# HV.net
KiCad netlist of a schematic drawn in Altium Designer
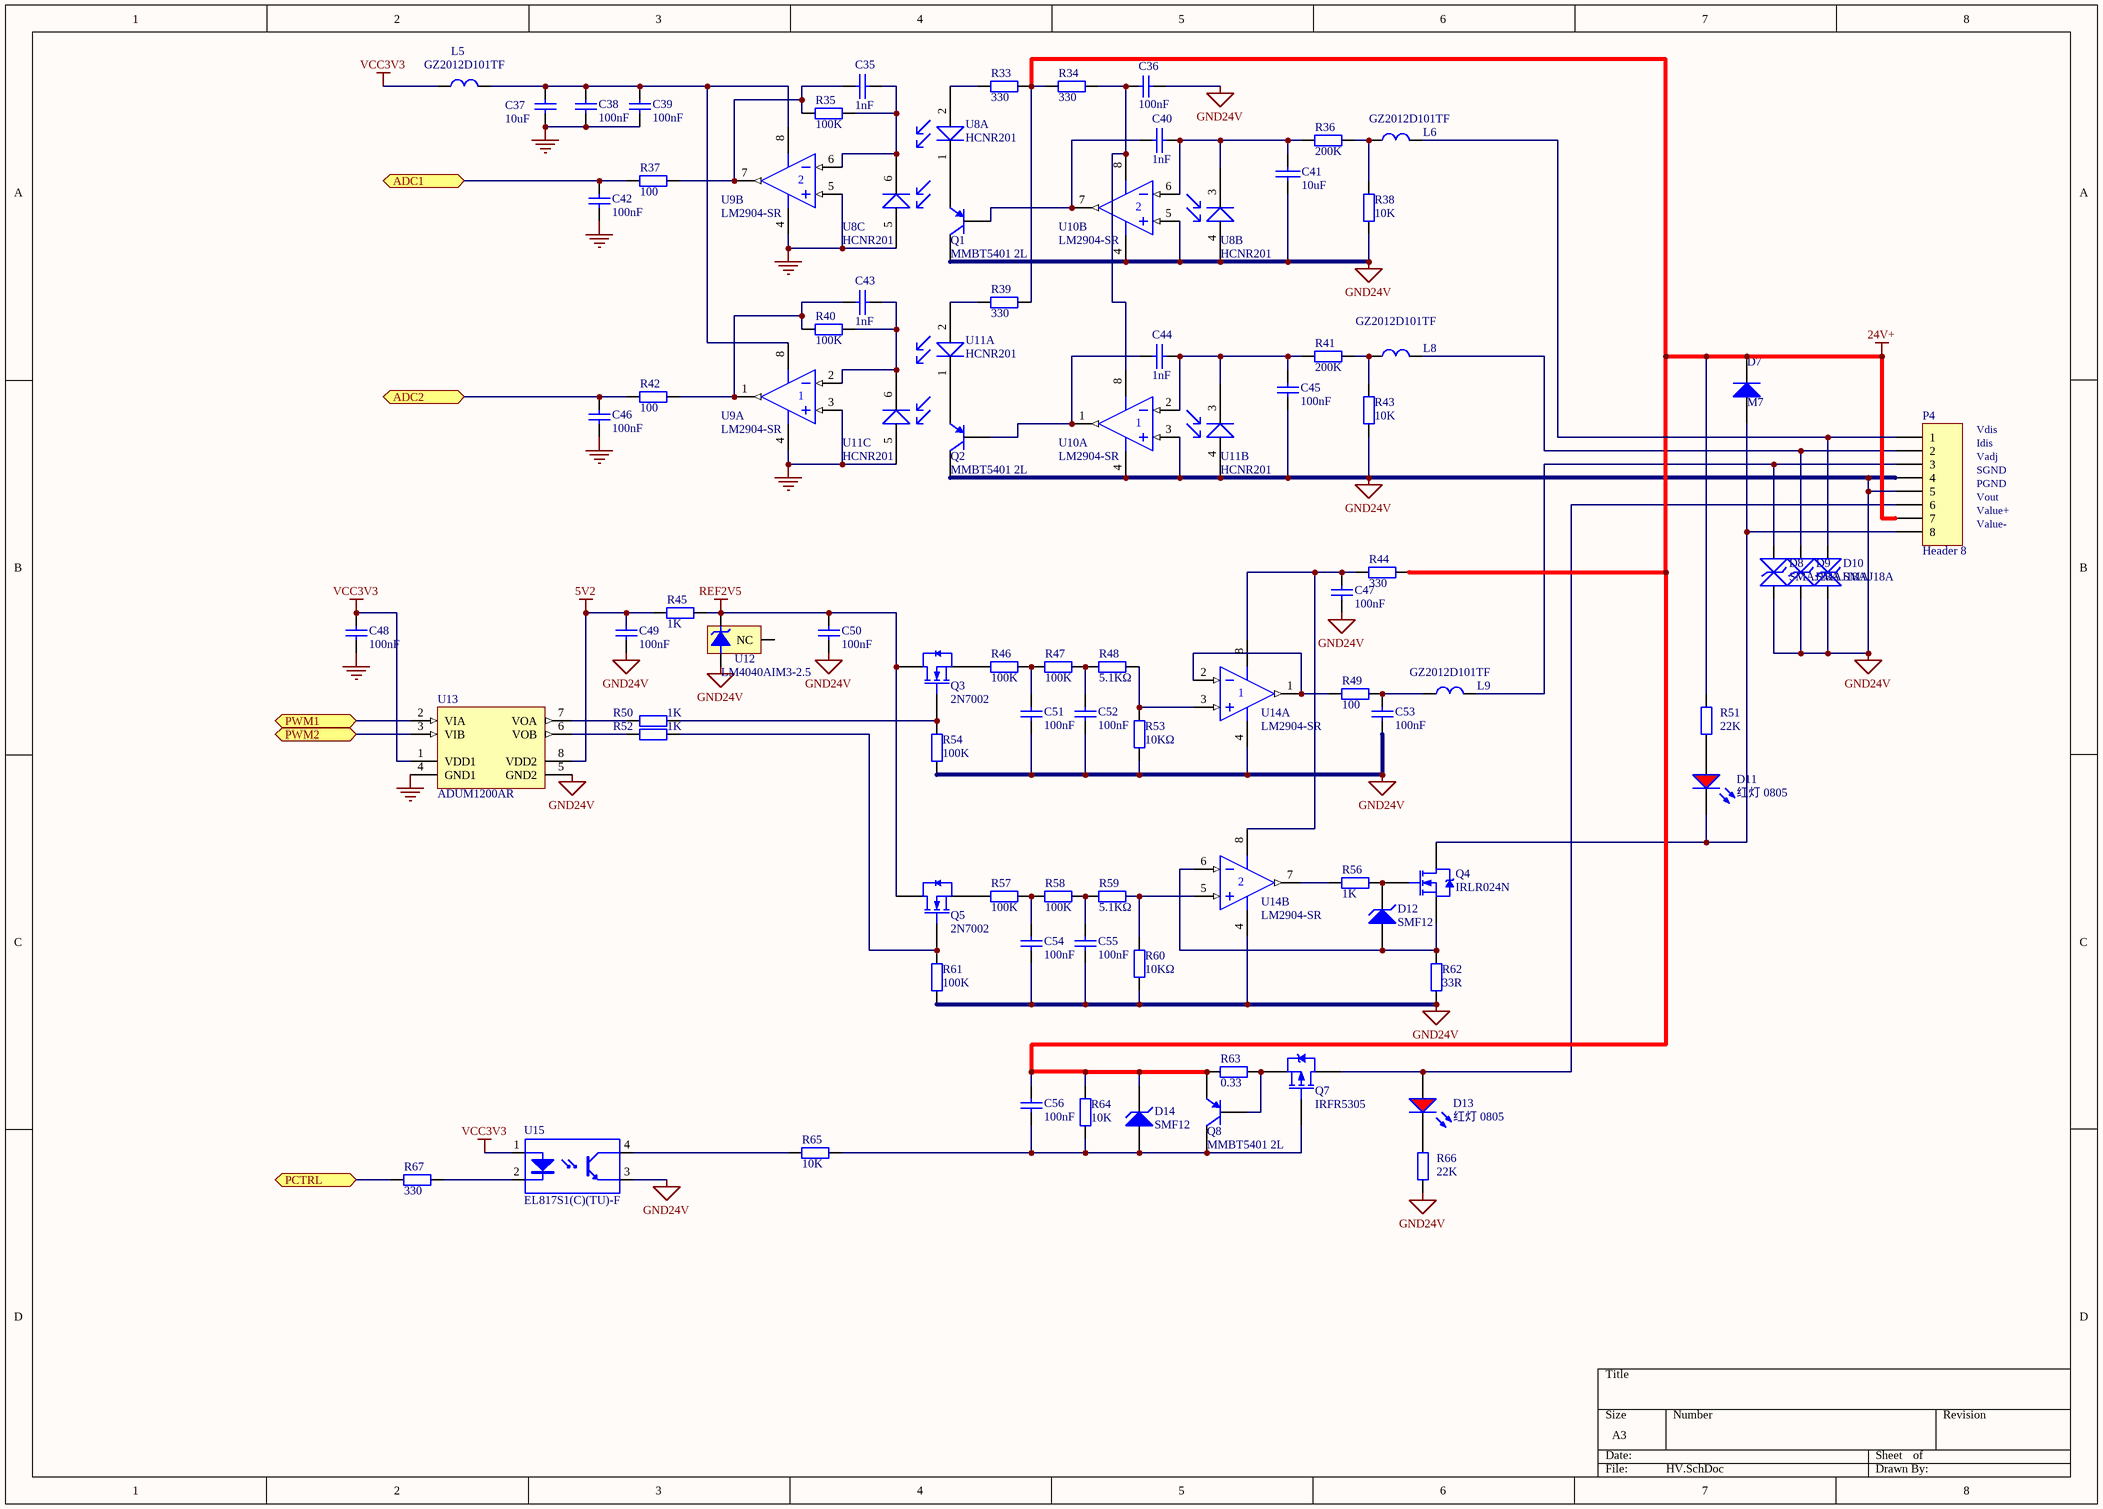
[diagram p0: HV.SchDoc]

(export (version "E")
  (design (tool "Eeschema 10.0.6"))
  (components
    (comp (ref "C35")
      (value "1nF")
      (footprint "0805_C")
      (description "Capacitor")
      (libsource (lib "*") (part "CAP"))
    )
    (comp (ref "C36")
      (value "100nF")
      (footprint "0805_C")
      (description "贴片电容")
      (libsource (lib "Miscellaneous Devices LC") (part "0805 100nF(104) 10% 50V"))
    )
    (comp (ref "C37")
      (value "10uF")
      (footprint "0805_C")
      (description "贴片电容")
      (libsource (lib "Miscellaneous Devices LC") (part "1206 10uF (106) 10% 50V"))
    )
    (comp (ref "C38")
      (value "100nF")
      (footprint "0805_C")
      (description "贴片电容")
      (libsource (lib "Miscellaneous Devices LC") (part "0805 100nF(104) 10% 50V"))
    )
    (comp (ref "C39")
      (value "100nF")
      (footprint "0805_C")
      (description "贴片电容")
      (libsource (lib "Miscellaneous Devices LC") (part "0805 100nF(104) 10% 50V"))
    )
    (comp (ref "C40")
      (value "1nF")
      (footprint "0805_C")
      (description "Capacitor")
      (libsource (lib "*") (part "CAP"))
    )
    (comp (ref "C41")
      (value "10uF")
      (footprint "0805_C")
      (description "Capacitor")
      (libsource (lib "*") (part "CC"))
    )
    (comp (ref "C42")
      (value "100nF")
      (footprint "0805_C")
      (description "贴片电容")
      (libsource (lib "Miscellaneous Devices LC") (part "0805 100nF(104) 10% 50V"))
    )
    (comp (ref "C43")
      (value "1nF")
      (footprint "0805_C")
      (description "Capacitor")
      (libsource (lib "*") (part "CAP"))
    )
    (comp (ref "C44")
      (value "1nF")
      (footprint "0805_C")
      (description "Capacitor")
      (libsource (lib "*") (part "CAP"))
    )
    (comp (ref "C45")
      (value "100nF")
      (footprint "0805_C")
      (description "贴片电容")
      (libsource (lib "Miscellaneous Devices LC") (part "0805 100nF(104) 10% 50V"))
    )
    (comp (ref "C46")
      (value "100nF")
      (footprint "0805_C")
      (description "贴片电容")
      (libsource (lib "Miscellaneous Devices LC") (part "0805 100nF(104) 10% 50V"))
    )
    (comp (ref "C47")
      (value "100nF")
      (footprint "0805_C")
      (description "贴片电容")
      (libsource (lib "Miscellaneous Devices LC") (part "0805 100nF(104) 10% 50V"))
    )
    (comp (ref "C48")
      (value "100nF")
      (footprint "0805_C")
      (description "贴片电容")
      (libsource (lib "Miscellaneous Devices LC") (part "0805 100nF(104) 10% 50V"))
    )
    (comp (ref "C49")
      (value "100nF")
      (footprint "0805_C")
      (description "贴片电容")
      (libsource (lib "Miscellaneous Devices LC") (part "0805 100nF(104) 10% 50V"))
    )
    (comp (ref "C50")
      (value "100nF")
      (footprint "0805_C")
      (description "贴片电容")
      (libsource (lib "Miscellaneous Devices LC") (part "0805 100nF(104) 10% 50V"))
    )
    (comp (ref "C51")
      (value "100nF")
      (footprint "0805_C")
      (description "贴片电容")
      (libsource (lib "Miscellaneous Devices LC") (part "0805 100nF(104) 10% 50V"))
    )
    (comp (ref "C52")
      (value "100nF")
      (footprint "0805_C")
      (description "贴片电容")
      (libsource (lib "Miscellaneous Devices LC") (part "0805 100nF(104) 10% 50V"))
    )
    (comp (ref "C53")
      (value "100nF")
      (footprint "0805_C")
      (description "贴片电容")
      (libsource (lib "Miscellaneous Devices LC") (part "0805 100nF(104) 10% 50V"))
    )
    (comp (ref "C54")
      (value "100nF")
      (footprint "0805_C")
      (description "贴片电容")
      (libsource (lib "Miscellaneous Devices LC") (part "0805 100nF(104) 10% 50V"))
    )
    (comp (ref "C55")
      (value "100nF")
      (footprint "0805_C")
      (description "贴片电容")
      (libsource (lib "Miscellaneous Devices LC") (part "0805 100nF(104) 10% 50V"))
    )
    (comp (ref "C56")
      (value "100nF")
      (footprint "0805_C")
      (description "贴片电容")
      (libsource (lib "Miscellaneous Devices LC") (part "0805 100nF(104) 10% 50V"))
    )
    (comp (ref "D7")
      (value "M7")
      (footprint "SMA(DO-214AC)_S1")
      (description "二极管")
      (libsource (lib "Miscellaneous Devices LC") (part "SMA(DO-214AC) M7"))
    )
    (comp (ref "D8") (value "SMAJ18A") (footprint "SMA") (libsource (lib "IC") (part "TVS")))
    (comp (ref "D9") (value "SMAJ18A") (footprint "SMA") (libsource (lib "IC") (part "TVS")))
    (comp (ref "D10") (value "SMAJ18A") (footprint "SMA") (libsource (lib "IC") (part "TVS")))
    (comp (ref "D11")
      (value "红灯 0805")
      (footprint "0805_LED_S1")
      (description "发光二极管")
      (libsource (lib "Miscellaneous Devices LC") (part "0805 红灯"))
    )
    (comp (ref "D12")
      (value "SMF12")
      (footprint "Miscellaneous Devices LC:SOD-123")
      (description "Zener Diode")
      (fields (field (name "PUBLISHER") "Altium Limited"))
      (libsource (lib "Miscellaneous Devices") (part "D Zener"))
    )
    (comp (ref "D13")
      (value "红灯 0805")
      (footprint "0805_LED_S1")
      (description "发光二极管")
      (libsource (lib "Miscellaneous Devices LC") (part "0805 红灯"))
    )
    (comp (ref "D14")
      (value "SMF12")
      (footprint "Miscellaneous Devices LC:SOD-123")
      (description "Zener Diode")
      (fields (field (name "PUBLISHER") "Altium Limited"))
      (libsource (lib "Miscellaneous Devices") (part "D Zener"))
    )
    (comp (ref "L5") (value "GZ2012D101TF") (footprint "0805_L") (libsource (lib "Devices") (part "L1")))
    (comp (ref "L6") (value "GZ2012D101TF") (footprint "0805_L") (libsource (lib "Devices") (part "L1")))
    (comp (ref "L8") (value "GZ2012D101TF") (footprint "0805_L") (libsource (lib "Devices") (part "L1")))
    (comp (ref "L9") (value "GZ2012D101TF") (footprint "0805_L") (libsource (lib "") (part "L1_1")))
    (comp (ref "P4")
      (value "Header 8")
      (footprint "MC1.5/8-ST-3.81")
      (description "Header, 8-Pin")
      (fields (field (name "PUBLISHER") "Altium Limited"))
      (libsource (lib "Miscellaneous Connectors") (part "Header 8"))
    )
    (comp (ref "Q1")
      (value "MMBT5401 2L")
      (footprint "SOT-23(SOT-23-3)")
      (description "三极管")
      (libsource (lib "Miscellaneous Devices LC") (part "SOT-23 MMBT5401 2L"))
    )
    (comp (ref "Q2")
      (value "MMBT5401 2L")
      (footprint "SOT-23(SOT-23-3)")
      (description "三极管")
      (libsource (lib "Miscellaneous Devices LC") (part "SOT-23 MMBT5401 2L"))
    )
    (comp (ref "Q3")
      (value "2N7002")
      (footprint "SOT-23(SOT-23-3)")
      (description "MOS(场效应管)")
      (libsource (lib "Miscellaneous Devices LC") (part "2N7002 7002"))
    )
    (comp (ref "Q4")
      (value "IRLR024N")
      (footprint "TO-252AA_N")
      (description "HEXFET Power MOSFET")
      (fields (field (name "PUBLISHER") "Altium Limited"))
      (libsource (lib "IR Discrete MOSFET - Power") (part "IRLR024N"))
    )
    (comp (ref "Q5")
      (value "2N7002")
      (footprint "SOT-23(SOT-23-3)")
      (description "MOS(场效应管)")
      (libsource (lib "Miscellaneous Devices LC") (part "2N7002 7002"))
    )
    (comp (ref "Q7")
      (value "IRFR5305")
      (footprint "TO-252AA_N")
      (description "HEXFET Power MOSFET")
      (fields (field (name "PUBLISHER") "Altium Limited"))
      (libsource (lib "IR Discrete MOSFET - Power") (part "IRFR5305"))
    )
    (comp (ref "Q8")
      (value "MMBT5401 2L")
      (footprint "SOT-23(SOT-23-3)")
      (description "三极管")
      (libsource (lib "Miscellaneous Devices LC") (part "SOT-23 MMBT5401 2L"))
    )
    (comp (ref "R33")
      (value "330")
      (footprint "0805_R")
      (description "Resistor")
      (fields (field (name "PUBLISHER") "Altium Limited"))
      (libsource (lib "") (part "Res2_1"))
    )
    (comp (ref "R34")
      (value "330")
      (footprint "0805_R")
      (description "Resistor")
      (fields (field (name "PUBLISHER") "Altium Limited"))
      (libsource (lib "") (part "Res2_1"))
    )
    (comp (ref "R35")
      (value "100K")
      (footprint "0805_R")
      (description "Resistor")
      (fields (field (name "PUBLISHER") "Altium Limited"))
      (libsource (lib "Miscellaneous Devices") (part "Res2"))
    )
    (comp (ref "R36")
      (value "200K")
      (footprint "0805_R")
      (description "Resistor")
      (fields (field (name "PUBLISHER") "Altium Limited"))
      (libsource (lib "Miscellaneous Devices") (part "Res2"))
    )
    (comp (ref "R37")
      (value "100")
      (footprint "0805_R")
      (description "Resistor")
      (fields (field (name "PUBLISHER") "Altium Limited"))
      (libsource (lib "") (part "Res2_1"))
    )
    (comp (ref "R38")
      (value "10K")
      (footprint "0805_R")
      (description "Resistor")
      (fields (field (name "PUBLISHER") "Altium Limited"))
      (libsource (lib "") (part "Res2_2"))
    )
    (comp (ref "R39")
      (value "330")
      (footprint "0805_R")
      (description "Resistor")
      (fields (field (name "PUBLISHER") "Altium Limited"))
      (libsource (lib "") (part "Res2_1"))
    )
    (comp (ref "R40")
      (value "100K")
      (footprint "0805_R")
      (description "Resistor")
      (fields (field (name "PUBLISHER") "Altium Limited"))
      (libsource (lib "Miscellaneous Devices") (part "Res2"))
    )
    (comp (ref "R41")
      (value "200K")
      (footprint "0805_R")
      (description "Resistor")
      (fields (field (name "PUBLISHER") "Altium Limited"))
      (libsource (lib "Miscellaneous Devices") (part "Res2"))
    )
    (comp (ref "R42")
      (value "100")
      (footprint "0805_R")
      (description "Resistor")
      (fields (field (name "PUBLISHER") "Altium Limited"))
      (libsource (lib "") (part "Res2_1"))
    )
    (comp (ref "R43")
      (value "10K")
      (footprint "0805_R")
      (description "Resistor")
      (fields (field (name "PUBLISHER") "Altium Limited"))
      (libsource (lib "") (part "Res2_2"))
    )
    (comp (ref "R44")
      (value "330")
      (footprint "0805_R")
      (description "贴片电阻")
      (libsource (lib "Miscellaneous Devices LC") (part "0805 100Ω (1000) 1%"))
    )
    (comp (ref "R45")
      (value "1K")
      (footprint "0805_R")
      (description "贴片电阻")
      (libsource (lib "") (part "0805 100KΩ (1003) 1%_1"))
    )
    (comp (ref "R46")
      (value "100K")
      (footprint "0805_R")
      (description "贴片电阻")
      (libsource (lib "") (part "0805 100KΩ (1003) 1%_1"))
    )
    (comp (ref "R47")
      (value "100K")
      (footprint "0805_R")
      (description "贴片电阻")
      (libsource (lib "") (part "0805 100KΩ (1003) 1%_1"))
    )
    (comp (ref "R48")
      (value "5.1KΩ")
      (footprint "0805_R")
      (description "贴片电阻")
      (libsource (lib "Miscellaneous Devices LC") (part "0805 5.1KΩ (5101) 1%"))
    )
    (comp (ref "R49")
      (value "100")
      (footprint "0805_R")
      (description "贴片电阻")
      (libsource (lib "") (part "0805 100KΩ (1003) 1%_1"))
    )
    (comp (ref "R50")
      (value "1K")
      (footprint "0805_R")
      (description "贴片电阻")
      (libsource (lib "") (part "0805 100KΩ (1003) 1%_2"))
    )
    (comp (ref "R51")
      (value "22K")
      (footprint "R0805")
      (description "贴片电阻")
      (libsource (lib "电阻") (part "RMK2012KBxxx（10～1M）F"))
    )
    (comp (ref "R52")
      (value "1K")
      (footprint "0805_R")
      (description "贴片电阻")
      (libsource (lib "") (part "0805 100KΩ (1003) 1%_2"))
    )
    (comp (ref "R53")
      (value "10KΩ")
      (footprint "0805_R")
      (description "贴片电阻")
      (libsource (lib "Miscellaneous Devices LC") (part "0805 10KΩ (1002) 1%"))
    )
    (comp (ref "R54")
      (value "100K")
      (footprint "0805_R")
      (description "贴片电阻")
      (libsource (lib "Miscellaneous Devices LC") (part "0805 100KΩ (1003) 1%"))
    )
    (comp (ref "R56")
      (value "1K")
      (footprint "0805_R")
      (description "贴片电阻")
      (libsource (lib "") (part "0805 100KΩ (1003) 1%_1"))
    )
    (comp (ref "R57")
      (value "100K")
      (footprint "0805_R")
      (description "贴片电阻")
      (libsource (lib "") (part "0805 100KΩ (1003) 1%_1"))
    )
    (comp (ref "R58")
      (value "100K")
      (footprint "0805_R")
      (description "贴片电阻")
      (libsource (lib "") (part "0805 100KΩ (1003) 1%_1"))
    )
    (comp (ref "R59")
      (value "5.1KΩ")
      (footprint "0805_R")
      (description "贴片电阻")
      (libsource (lib "Miscellaneous Devices LC") (part "0805 5.1KΩ (5101) 1%"))
    )
    (comp (ref "R60")
      (value "10KΩ")
      (footprint "0805_R")
      (description "贴片电阻")
      (libsource (lib "Miscellaneous Devices LC") (part "0805 10KΩ (1002) 1%"))
    )
    (comp (ref "R61")
      (value "100K")
      (footprint "0805_R")
      (description "贴片电阻")
      (libsource (lib "Miscellaneous Devices LC") (part "0805 100KΩ (1003) 1%"))
    )
    (comp (ref "R62")
      (value "33R")
      (footprint "R2512")
      (description "Resistor")
      (fields (field (name "PUBLISHER") "Altium Limited"))
      (libsource (lib "") (part "Res2_4"))
    )
    (comp (ref "R63")
      (value "0.33")
      (footprint "R2512")
      (description "Resistor")
      (fields (field (name "PUBLISHER") "Altium Limited"))
      (libsource (lib "") (part "Res2_3"))
    )
    (comp (ref "R64")
      (value "10K")
      (footprint "0805_R")
      (description "Resistor")
      (fields (field (name "PUBLISHER") "Altium Limited"))
      (libsource (lib "") (part "Res2_4"))
    )
    (comp (ref "R65")
      (value "10K")
      (footprint "0805_R")
      (description "Resistor")
      (fields (field (name "PUBLISHER") "Altium Limited"))
      (libsource (lib "") (part "Res2_3"))
    )
    (comp (ref "R66")
      (value "22K")
      (footprint "0805_R")
      (description "贴片电阻")
      (libsource (lib "电阻") (part "RMK2012KBxxx（10～1M）F"))
    )
    (comp (ref "R67")
      (value "330")
      (footprint "0805_R")
      (description "Resistor")
      (fields (field (name "PUBLISHER") "Altium Limited"))
      (libsource (lib "") (part "Res2_5"))
    )
    (comp (ref "U8") (value "HCNR201") (footprint "SMD-8_9.0mm") (libsource (lib "*") (part "HCNR201")))
    (comp (ref "U9")
      (value "LM2904-SR")
      (footprint "SOIC-8_150mil")
      (description "Dual Low-Power Operational Amplifier")
      (fields (field (name "PUBLISHER") "Altium Limited"))
      (libsource (lib "Miscellaneous Devices LC") (part "LM2904D"))
    )
    (comp (ref "U10")
      (value "LM2904-SR")
      (footprint "SOIC-8_150mil")
      (description "Dual Low-Power Operational Amplifier")
      (fields (field (name "PUBLISHER") "Altium Limited"))
      (libsource (lib "Miscellaneous Devices LC") (part "LM2904D"))
    )
    (comp (ref "U11") (value "HCNR201") (footprint "SMD-8_9.0mm") (libsource (lib "*") (part "HCNR201")))
    (comp (ref "U12")
      (value "LM4040AIM3-2.5")
      (footprint "MF03A_N")
      (description "Precision Micropower Shunt Voltage Reference, 3-pin SOT-23")
      (fields (field (name "MANUFACTURER") "National Semiconductor"))
      (libsource (lib "National Semiconductor Voltage Reference") (part "LM4040AIM3-2.5"))
    )
    (comp (ref "U13")
      (value "ADUM1200AR")
      (footprint "ADI-R-8_N")
      (fields (field (name "MANUFACTURER") "Analog Devices"))
      (libsource (lib "Analog Devices Interface and Isolation Digital Isolators") (part "ADUM1200AR"))
    )
    (comp (ref "U14")
      (value "LM2904-SR")
      (footprint "SOIC-8_150mil")
      (description "Dual Low-Power Operational Amplifier")
      (fields (field (name "PUBLISHER") "Altium Limited"))
      (libsource (lib "Miscellaneous Devices LC") (part "LM2904D"))
    )
    (comp (ref "U15")
      (value "EL817S1(C)(TU)-F")
      (footprint "LC-SMD-4")
      (libsource (lib "IC") (part "TLP521"))
    )
  )
  (nets
    (net (code "1") (name "/ADC1") (class "Default")
      (node (ref "C42") (pin "2") (pinfunction "2_2") (pintype "passive"))
      (node (ref "R37") (pin "2") (pinfunction "2_2") (pintype "passive"))
    )
    (net (code "2") (name "/ADC2") (class "Default")
      (node (ref "C46") (pin "2") (pinfunction "2_2") (pintype "passive"))
      (node (ref "R42") (pin "2") (pinfunction "2_2") (pintype "passive"))
    )
    (net (code "3") (name "/PCTRL") (class "Default")
      (node (ref "R67") (pin "1") (pinfunction "1_1") (pintype "passive"))
    )
    (net (code "4") (name "/PWM1") (class "Default")
      (node (ref "U13") (pin "2") (pinfunction "VIA_2") (pintype "input"))
    )
    (net (code "5") (name "/PWM2") (class "Default")
      (node (ref "U13") (pin "3") (pinfunction "VIB_3") (pintype "input"))
    )
    (net (code "6") (name "5V2") (class "Default")
      (node (ref "C49") (pin "2") (pinfunction "2_2") (pintype "passive"))
      (node (ref "R45") (pin "2") (pinfunction "2_2") (pintype "passive"))
      (node (ref "U13") (pin "8") (pinfunction "VDD2_8") (pintype "power_in"))
    )
    (net (code "7") (name "24V+") (class "Default")
      (node (ref "C56") (pin "2") (pinfunction "2_2") (pintype "passive"))
      (node (ref "D14") (pin "2") (pinfunction "K_2") (pintype "passive"))
      (node (ref "D7") (pin "2") (pinfunction "K_2") (pintype "passive"))
      (node (ref "P4") (pin "7") (pinfunction "7_7") (pintype "passive"))
      (node (ref "Q8") (pin "2") (pinfunction "E_2") (pintype "passive"))
      (node (ref "R33") (pin "1") (pinfunction "1_1") (pintype "passive"))
      (node (ref "R34") (pin "2") (pinfunction "2_2") (pintype "passive"))
      (node (ref "R39") (pin "1") (pinfunction "1_1") (pintype "passive"))
      (node (ref "R44") (pin "1") (pinfunction "1_1") (pintype "passive"))
      (node (ref "R51") (pin "1") (pinfunction "1_1") (pintype "passive"))
      (node (ref "R63") (pin "2") (pinfunction "2_2") (pintype "passive"))
      (node (ref "R64") (pin "2") (pinfunction "2_2") (pintype "passive"))
    )
    (net (code "8") (name "GND") (class "Default")
      (node (ref "C37") (pin "1") (pinfunction "1_1") (pintype "passive"))
      (node (ref "C38") (pin "1") (pinfunction "1_1") (pintype "passive"))
      (node (ref "C39") (pin "1") (pinfunction "1_1") (pintype "passive"))
      (node (ref "C42") (pin "1") (pinfunction "1_1") (pintype "passive"))
      (node (ref "C46") (pin "1") (pinfunction "1_1") (pintype "passive"))
      (node (ref "C48") (pin "1") (pinfunction "1_1") (pintype "passive"))
      (node (ref "U11") (pin "5") (pinfunction "+_5") (pintype "passive"))
      (node (ref "U13") (pin "4") (pinfunction "GND1_4") (pintype "power_in"))
      (node (ref "U8") (pin "5") (pinfunction "+_5") (pintype "passive"))
      (node (ref "U9") (pin "3") (pinfunction "IN+_3") (pintype "input"))
      (node (ref "U9") (pin "4") (pinfunction "V-_4") (pintype "power_in"))
      (node (ref "U9") (pin "5") (pinfunction "IN+_5") (pintype "input"))
    )
    (net (code "9") (name "GND24V") (class "Default")
      (node (ref "C36") (pin "1") (pinfunction "1_1") (pintype "passive"))
      (node (ref "C41") (pin "1") (pinfunction "1_1") (pintype "passive"))
      (node (ref "C45") (pin "1") (pinfunction "1_1") (pintype "passive"))
      (node (ref "C47") (pin "1") (pinfunction "1_1") (pintype "passive"))
      (node (ref "C49") (pin "1") (pinfunction "1_1") (pintype "passive"))
      (node (ref "C50") (pin "1") (pinfunction "1_1") (pintype "passive"))
      (node (ref "C51") (pin "1") (pinfunction "1_1") (pintype "passive"))
      (node (ref "C52") (pin "1") (pinfunction "1_1") (pintype "passive"))
      (node (ref "C53") (pin "1") (pinfunction "1_1") (pintype "passive"))
      (node (ref "C54") (pin "1") (pinfunction "1_1") (pintype "passive"))
      (node (ref "C55") (pin "1") (pinfunction "1_1") (pintype "passive"))
      (node (ref "D10") (pin "1") (pinfunction "1_1") (pintype "passive"))
      (node (ref "D8") (pin "1") (pinfunction "1_1") (pintype "passive"))
      (node (ref "D9") (pin "1") (pinfunction "1_1") (pintype "passive"))
      (node (ref "P4") (pin "4") (pinfunction "4_4") (pintype "passive"))
      (node (ref "P4") (pin "5") (pinfunction "5_5") (pintype "passive"))
      (node (ref "Q1") (pin "3") (pinfunction "C_3") (pintype "passive"))
      (node (ref "Q2") (pin "3") (pinfunction "C_3") (pintype "passive"))
      (node (ref "R38") (pin "1") (pinfunction "1_1") (pintype "passive"))
      (node (ref "R43") (pin "1") (pinfunction "1_1") (pintype "passive"))
      (node (ref "R53") (pin "2") (pinfunction "2_2") (pintype "passive"))
      (node (ref "R54") (pin "2") (pinfunction "2_2") (pintype "passive"))
      (node (ref "R60") (pin "2") (pinfunction "2_2") (pintype "passive"))
      (node (ref "R61") (pin "2") (pinfunction "2_2") (pintype "passive"))
      (node (ref "R62") (pin "1") (pinfunction "1_1") (pintype "passive"))
      (node (ref "R66") (pin "2") (pinfunction "2_2") (pintype "passive"))
      (node (ref "U10") (pin "3") (pinfunction "IN+_3") (pintype "input"))
      (node (ref "U10") (pin "4") (pinfunction "V-_4") (pintype "power_in"))
      (node (ref "U10") (pin "5") (pinfunction "IN+_5") (pintype "input"))
      (node (ref "U11") (pin "4") (pinfunction "+_4") (pintype "passive"))
      (node (ref "U12") (pin "2") (pinfunction "-V_2") (pintype "passive"))
      (node (ref "U13") (pin "5") (pinfunction "GND2_5") (pintype "power_in"))
      (node (ref "U14") (pin "4") (pinfunction "V-_4") (pintype "power_in"))
      (node (ref "U15") (pin "3") (pinfunction "E_3") (pintype "passive"))
      (node (ref "U8") (pin "4") (pinfunction "+_4") (pintype "passive"))
    )
    (net (code "10") (name "Net-(C51-Pad2)") (class "Default")
      (node (ref "C51") (pin "2") (pinfunction "2_2") (pintype "passive"))
      (node (ref "R46") (pin "1") (pinfunction "1_1") (pintype "passive"))
      (node (ref "R47") (pin "2") (pinfunction "2_2") (pintype "passive"))
    )
    (net (code "11") (name "Net-(C52-Pad2)") (class "Default")
      (node (ref "C52") (pin "2") (pinfunction "2_2") (pintype "passive"))
      (node (ref "R47") (pin "1") (pinfunction "1_1") (pintype "passive"))
      (node (ref "R48") (pin "2") (pinfunction "2_2") (pintype "passive"))
    )
    (net (code "12") (name "Net-(C53-Pad2)") (class "Default")
      (node (ref "C53") (pin "2") (pinfunction "2_2") (pintype "passive"))
      (node (ref "L9") (pin "2") (pinfunction "2_2") (pintype "passive"))
      (node (ref "R49") (pin "1") (pinfunction "1_1") (pintype "passive"))
    )
    (net (code "13") (name "Net-(C54-Pad2)") (class "Default")
      (node (ref "C54") (pin "2") (pinfunction "2_2") (pintype "passive"))
      (node (ref "R57") (pin "1") (pinfunction "1_1") (pintype "passive"))
      (node (ref "R58") (pin "2") (pinfunction "2_2") (pintype "passive"))
    )
    (net (code "14") (name "Net-(C55-Pad2)") (class "Default")
      (node (ref "C55") (pin "2") (pinfunction "2_2") (pintype "passive"))
      (node (ref "R58") (pin "1") (pinfunction "1_1") (pintype "passive"))
      (node (ref "R59") (pin "2") (pinfunction "2_2") (pintype "passive"))
    )
    (net (code "15") (name "Net-(D7-A)") (class "Default")
      (node (ref "D11") (pin "K") (pinfunction "K_K") (pintype "passive"))
      (node (ref "D7") (pin "1") (pinfunction "A_1") (pintype "passive"))
      (node (ref "P4") (pin "8") (pinfunction "8_8") (pintype "passive"))
      (node (ref "Q4") (pin "4") (pinfunction "D_4") (pintype "passive"))
    )
    (net (code "16") (name "Net-(D8-Pad2)") (class "Default")
      (node (ref "D8") (pin "2") (pinfunction "2_2") (pintype "passive"))
      (node (ref "L9") (pin "1") (pinfunction "1_1") (pintype "passive"))
      (node (ref "P4") (pin "3") (pinfunction "3_3") (pintype "passive"))
    )
    (net (code "17") (name "Net-(D9-Pad2)") (class "Default")
      (node (ref "D9") (pin "2") (pinfunction "2_2") (pintype "passive"))
      (node (ref "L8") (pin "2") (pinfunction "2_2") (pintype "passive"))
      (node (ref "P4") (pin "2") (pinfunction "2_2") (pintype "passive"))
    )
    (net (code "18") (name "Net-(D10-Pad2)") (class "Default")
      (node (ref "D10") (pin "2") (pinfunction "2_2") (pintype "passive"))
      (node (ref "L6") (pin "2") (pinfunction "2_2") (pintype "passive"))
      (node (ref "P4") (pin "1") (pinfunction "1_1") (pintype "passive"))
    )
    (net (code "19") (name "Net-(D11-PadA)") (class "Default")
      (node (ref "D11") (pin "A") (pinfunction "A_A") (pintype "passive"))
      (node (ref "R51") (pin "2") (pinfunction "2_2") (pintype "passive"))
    )
    (net (code "20") (name "Net-(D12-A)") (class "Default")
      (node (ref "D12") (pin "1") (pinfunction "A_1") (pintype "passive"))
      (node (ref "Q4") (pin "3") (pinfunction "S_3") (pintype "passive"))
      (node (ref "R62") (pin "2") (pinfunction "2_2") (pintype "passive"))
      (node (ref "U14") (pin "6") (pinfunction "IN-_6") (pintype "input"))
    )
    (net (code "21") (name "Net-(D12-K)") (class "Default")
      (node (ref "D12") (pin "2") (pinfunction "K_2") (pintype "passive"))
      (node (ref "Q4") (pin "1") (pinfunction "G_1") (pintype "passive"))
      (node (ref "R56") (pin "1") (pinfunction "1_1") (pintype "passive"))
    )
    (net (code "22") (name "Net-(D13-PadK)") (class "Default")
      (node (ref "D13") (pin "K") (pinfunction "K_K") (pintype "passive"))
      (node (ref "R66") (pin "1") (pinfunction "1_1") (pintype "passive"))
    )
    (net (code "23") (name "Net-(D14-A)") (class "Default")
      (node (ref "C56") (pin "1") (pinfunction "1_1") (pintype "passive"))
      (node (ref "D14") (pin "1") (pinfunction "A_1") (pintype "passive"))
      (node (ref "Q7") (pin "1") (pinfunction "G_1") (pintype "passive"))
      (node (ref "Q8") (pin "3") (pinfunction "C_3") (pintype "passive"))
      (node (ref "R64") (pin "1") (pinfunction "1_1") (pintype "passive"))
      (node (ref "R65") (pin "1") (pinfunction "1_1") (pintype "passive"))
    )
    (net (code "24") (name "Net-(L6-Pad1)") (class "Default")
      (node (ref "L6") (pin "1") (pinfunction "1_1") (pintype "passive"))
      (node (ref "R36") (pin "2") (pinfunction "2_2") (pintype "passive"))
      (node (ref "R38") (pin "2") (pinfunction "2_2") (pintype "passive"))
    )
    (net (code "25") (name "Net-(L8-Pad1)") (class "Default")
      (node (ref "L8") (pin "1") (pinfunction "1_1") (pintype "passive"))
      (node (ref "R41") (pin "2") (pinfunction "2_2") (pintype "passive"))
      (node (ref "R43") (pin "2") (pinfunction "2_2") (pintype "passive"))
    )
    (net (code "26") (name "Net-(Q1-B)") (class "Default")
      (node (ref "C40") (pin "2") (pinfunction "2_2") (pintype "passive"))
      (node (ref "Q1") (pin "1") (pinfunction "B_1") (pintype "passive"))
      (node (ref "U10") (pin "7") (pinfunction "OUT_7") (pintype "output"))
    )
    (net (code "27") (name "Net-(Q1-E)") (class "Default")
      (node (ref "Q1") (pin "2") (pinfunction "E_2") (pintype "passive"))
      (node (ref "U8") (pin "1") (pinfunction "-_1") (pintype "passive"))
    )
    (net (code "28") (name "Net-(Q2-B)") (class "Default")
      (node (ref "C44") (pin "2") (pinfunction "2_2") (pintype "passive"))
      (node (ref "Q2") (pin "1") (pinfunction "B_1") (pintype "passive"))
      (node (ref "U10") (pin "1") (pinfunction "OUT_1") (pintype "output"))
    )
    (net (code "29") (name "Net-(Q2-E)") (class "Default")
      (node (ref "Q2") (pin "2") (pinfunction "E_2") (pintype "passive"))
      (node (ref "U11") (pin "1") (pinfunction "-_1") (pintype "passive"))
    )
    (net (code "30") (name "Net-(Q3-G)") (class "Default")
      (node (ref "Q3") (pin "1") (pinfunction "G_1") (pintype "passive"))
      (node (ref "R50") (pin "2") (pinfunction "2_2") (pintype "passive"))
      (node (ref "R54") (pin "1") (pinfunction "1_1") (pintype "passive"))
    )
    (net (code "31") (name "Net-(Q3-S)") (class "Default")
      (node (ref "Q3") (pin "2") (pinfunction "S_2") (pintype "passive"))
      (node (ref "R46") (pin "2") (pinfunction "2_2") (pintype "passive"))
    )
    (net (code "32") (name "Net-(Q5-G)") (class "Default")
      (node (ref "Q5") (pin "1") (pinfunction "G_1") (pintype "passive"))
      (node (ref "R52") (pin "2") (pinfunction "2_2") (pintype "passive"))
      (node (ref "R61") (pin "1") (pinfunction "1_1") (pintype "passive"))
    )
    (net (code "33") (name "Net-(Q5-S)") (class "Default")
      (node (ref "Q5") (pin "2") (pinfunction "S_2") (pintype "passive"))
      (node (ref "R57") (pin "2") (pinfunction "2_2") (pintype "passive"))
    )
    (net (code "34") (name "Net-(Q7-D)") (class "Default")
      (node (ref "D13") (pin "A") (pinfunction "A_A") (pintype "passive"))
      (node (ref "P4") (pin "6") (pinfunction "6_6") (pintype "passive"))
      (node (ref "Q7") (pin "4") (pinfunction "D_4") (pintype "passive"))
    )
    (net (code "35") (name "Net-(Q7-S)") (class "Default")
      (node (ref "Q7") (pin "3") (pinfunction "S_3") (pintype "passive"))
      (node (ref "Q8") (pin "1") (pinfunction "B_1") (pintype "passive"))
      (node (ref "R63") (pin "1") (pinfunction "1_1") (pintype "passive"))
    )
    (net (code "36") (name "Net-(U8A-+)") (class "Default")
      (node (ref "R33") (pin "2") (pinfunction "2_2") (pintype "passive"))
      (node (ref "U8") (pin "2") (pinfunction "+_2") (pintype "passive"))
    )
    (net (code "37") (name "Net-(U8C--)") (class "Default")
      (node (ref "C35") (pin "1") (pinfunction "1_1") (pintype "passive"))
      (node (ref "R35") (pin "2") (pinfunction "2_2") (pintype "passive"))
      (node (ref "U8") (pin "6") (pinfunction "-_6") (pintype "passive"))
      (node (ref "U9") (pin "6") (pinfunction "IN-_6") (pintype "input"))
    )
    (net (code "38") (name "Net-(U9A-OUT)") (class "Default")
      (node (ref "C43") (pin "2") (pinfunction "2_2") (pintype "passive"))
      (node (ref "R40") (pin "1") (pinfunction "1_1") (pintype "passive"))
      (node (ref "R42") (pin "1") (pinfunction "1_1") (pintype "passive"))
      (node (ref "U9") (pin "1") (pinfunction "OUT_1") (pintype "output"))
    )
    (net (code "39") (name "Net-(U9A-V+)") (class "Default")
      (node (ref "C37") (pin "2") (pinfunction "2_2") (pintype "passive"))
      (node (ref "C38") (pin "2") (pinfunction "2_2") (pintype "passive"))
      (node (ref "C39") (pin "2") (pinfunction "2_2") (pintype "passive"))
      (node (ref "L5") (pin "2") (pinfunction "2_2") (pintype "passive"))
      (node (ref "U9") (pin "8") (pinfunction "V+_8") (pintype "power_in"))
    )
    (net (code "40") (name "Net-(U9B-OUT)") (class "Default")
      (node (ref "C35") (pin "2") (pinfunction "2_2") (pintype "passive"))
      (node (ref "R35") (pin "1") (pinfunction "1_1") (pintype "passive"))
      (node (ref "R37") (pin "1") (pinfunction "1_1") (pintype "passive"))
      (node (ref "U9") (pin "7") (pinfunction "OUT_7") (pintype "output"))
    )
    (net (code "41") (name "Net-(U10A-IN-)") (class "Default")
      (node (ref "C44") (pin "1") (pinfunction "1_1") (pintype "passive"))
      (node (ref "C45") (pin "2") (pinfunction "2_2") (pintype "passive"))
      (node (ref "R41") (pin "1") (pinfunction "1_1") (pintype "passive"))
      (node (ref "U10") (pin "2") (pinfunction "IN-_2") (pintype "input"))
      (node (ref "U11") (pin "3") (pinfunction "-_3") (pintype "passive"))
    )
    (net (code "42") (name "Net-(U10A-V+)") (class "Default")
      (node (ref "C36") (pin "2") (pinfunction "2_2") (pintype "passive"))
      (node (ref "R34") (pin "1") (pinfunction "1_1") (pintype "passive"))
      (node (ref "U10") (pin "8") (pinfunction "V+_8") (pintype "power_in"))
    )
    (net (code "43") (name "Net-(U10B-IN-)") (class "Default")
      (node (ref "C40") (pin "1") (pinfunction "1_1") (pintype "passive"))
      (node (ref "C41") (pin "2") (pinfunction "2_2") (pintype "passive"))
      (node (ref "R36") (pin "1") (pinfunction "1_1") (pintype "passive"))
      (node (ref "U10") (pin "6") (pinfunction "IN-_6") (pintype "input"))
      (node (ref "U8") (pin "3") (pinfunction "-_3") (pintype "passive"))
    )
    (net (code "44") (name "Net-(U11A-+)") (class "Default")
      (node (ref "R39") (pin "2") (pinfunction "2_2") (pintype "passive"))
      (node (ref "U11") (pin "2") (pinfunction "+_2") (pintype "passive"))
    )
    (net (code "45") (name "Net-(U11C--)") (class "Default")
      (node (ref "C43") (pin "1") (pinfunction "1_1") (pintype "passive"))
      (node (ref "R40") (pin "2") (pinfunction "2_2") (pintype "passive"))
      (node (ref "U11") (pin "6") (pinfunction "-_6") (pintype "passive"))
      (node (ref "U9") (pin "2") (pinfunction "IN-_2") (pintype "input"))
    )
    (net (code "46") (name "Net-(U13-VOA)") (class "Default")
      (node (ref "R50") (pin "1") (pinfunction "1_1") (pintype "passive"))
      (node (ref "U13") (pin "7") (pinfunction "VOA_7") (pintype "output"))
    )
    (net (code "47") (name "Net-(U13-VOB)") (class "Default")
      (node (ref "R52") (pin "1") (pinfunction "1_1") (pintype "passive"))
      (node (ref "U13") (pin "6") (pinfunction "VOB_6") (pintype "output"))
    )
    (net (code "48") (name "Net-(U14A-IN+)") (class "Default")
      (node (ref "R48") (pin "1") (pinfunction "1_1") (pintype "passive"))
      (node (ref "R53") (pin "1") (pinfunction "1_1") (pintype "passive"))
      (node (ref "U14") (pin "3") (pinfunction "IN+_3") (pintype "input"))
    )
    (net (code "49") (name "Net-(U14A-IN-)") (class "Default")
      (node (ref "R49") (pin "2") (pinfunction "2_2") (pintype "passive"))
      (node (ref "U14") (pin "1") (pinfunction "OUT_1") (pintype "output"))
      (node (ref "U14") (pin "2") (pinfunction "IN-_2") (pintype "input"))
    )
    (net (code "50") (name "Net-(U14A-V+)") (class "Default")
      (node (ref "C47") (pin "2") (pinfunction "2_2") (pintype "passive"))
      (node (ref "R44") (pin "2") (pinfunction "2_2") (pintype "passive"))
      (node (ref "U14") (pin "8") (pinfunction "V+_8") (pintype "power_in"))
    )
    (net (code "51") (name "Net-(U14B-IN+)") (class "Default")
      (node (ref "R59") (pin "1") (pinfunction "1_1") (pintype "passive"))
      (node (ref "R60") (pin "1") (pinfunction "1_1") (pintype "passive"))
      (node (ref "U14") (pin "5") (pinfunction "IN+_5") (pintype "input"))
    )
    (net (code "52") (name "Net-(U14B-OUT)") (class "Default")
      (node (ref "R56") (pin "2") (pinfunction "2_2") (pintype "passive"))
      (node (ref "U14") (pin "7") (pinfunction "OUT_7") (pintype "output"))
    )
    (net (code "53") (name "Net-(U15-C)") (class "Default")
      (node (ref "R65") (pin "2") (pinfunction "2_2") (pintype "passive"))
      (node (ref "U15") (pin "4") (pinfunction "C_4") (pintype "passive"))
    )
    (net (code "54") (name "Net-(U15-K)") (class "Default")
      (node (ref "R67") (pin "2") (pinfunction "2_2") (pintype "passive"))
      (node (ref "U15") (pin "2") (pinfunction "K_2") (pintype "passive"))
    )
    (net (code "55") (name "REF2V5") (class "Default")
      (node (ref "C50") (pin "2") (pinfunction "2_2") (pintype "passive"))
      (node (ref "Q3") (pin "3") (pinfunction "D_3") (pintype "passive"))
      (node (ref "Q5") (pin "3") (pinfunction "D_3") (pintype "passive"))
      (node (ref "R45") (pin "1") (pinfunction "1_1") (pintype "passive"))
      (node (ref "U12") (pin "1") (pinfunction "+V_1") (pintype "passive"))
    )
    (net (code "56") (name "VCC3V3") (class "Default")
      (node (ref "C48") (pin "2") (pinfunction "2_2") (pintype "passive"))
      (node (ref "L5") (pin "1") (pinfunction "1_1") (pintype "passive"))
      (node (ref "U13") (pin "1") (pinfunction "VDD1_1") (pintype "power_in"))
      (node (ref "U15") (pin "1") (pinfunction "A_1") (pintype "passive"))
    )
    (net (code "57") (name "unconnected-(U12-NC-Pad3)") (class "Default")
      (node (ref "U12") (pin "3") (pinfunction "NC_3") (pintype "passive"))
    )
  )
)
